# 09_iMX_8X_SD_CARD_V2X.net
KiCad netlist of a schematic drawn in Altium Designer
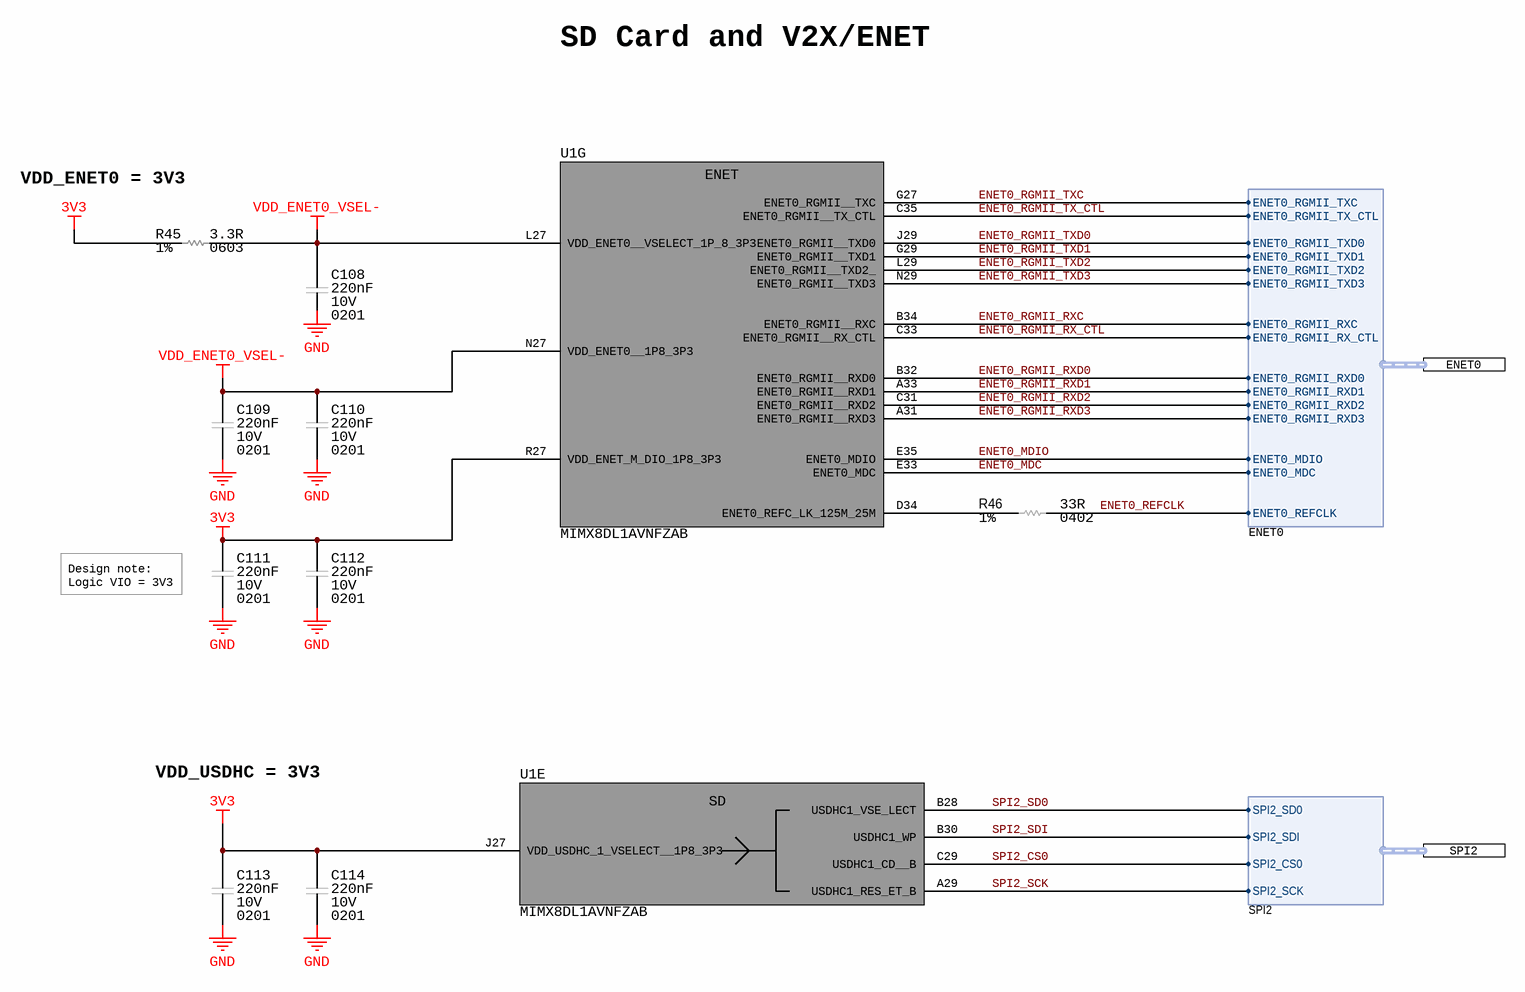
[diagram p0: 09_iMX 8X_SD CARD & V2X.SchDoc]

(export (version "E")
  (design (tool "Eeschema 10.0.6"))
  (components
    (comp (ref "C108")
      (value "LMK063BJ224MP-F")
      (footprint "CAP_0201_CAPC0603X03N")
      (description "Multilayer Ceramic Capacitors (High dielectric type), 10V, 0.22 uF, ± 20 %, 0201, X5R, RoHS")
      (fields
        (field (name "MANUFACTURER") "Taiyo Yuden")
        (field (name "TOLERANCE") "20%")
        (field (name "VOLTAGE RATING (DC)") "10V")
        (field (name "CAPACITANCE") "220nF")
        (field (name "CASE/PACKAGE") "0201")
      )
      (libsource (lib "Electronic Devices_LIB") (part "CAP_0.22UF_10V_X5R_0201"))
    )
    (comp (ref "C109")
      (value "LMK063BJ224MP-F")
      (footprint "CAP_0201_CAPC0603X03N")
      (description "Multilayer Ceramic Capacitors (High dielectric type), 10V, 0.22 uF, ± 20 %, 0201, X5R, RoHS")
      (fields
        (field (name "MANUFACTURER") "Taiyo Yuden")
        (field (name "TOLERANCE") "20%")
        (field (name "VOLTAGE RATING (DC)") "10V")
        (field (name "CAPACITANCE") "220nF")
        (field (name "CASE/PACKAGE") "0201")
      )
      (libsource (lib "Electronic Devices_LIB") (part "CAP_0.22UF_10V_X5R_0201"))
    )
    (comp (ref "C110")
      (value "LMK063BJ224MP-F")
      (footprint "CAP_0201_CAPC0603X03N")
      (description "Multilayer Ceramic Capacitors (High dielectric type), 10V, 0.22 uF, ± 20 %, 0201, X5R, RoHS")
      (fields
        (field (name "MANUFACTURER") "Taiyo Yuden")
        (field (name "TOLERANCE") "20%")
        (field (name "VOLTAGE RATING (DC)") "10V")
        (field (name "CAPACITANCE") "220nF")
        (field (name "CASE/PACKAGE") "0201")
      )
      (libsource (lib "Electronic Devices_LIB") (part "CAP_0.22UF_10V_X5R_0201"))
    )
    (comp (ref "C111")
      (value "LMK063BJ224MP-F")
      (footprint "CAP_0201_CAPC0603X03N")
      (description "Multilayer Ceramic Capacitors (High dielectric type), 10V, 0.22 uF, ± 20 %, 0201, X5R, RoHS")
      (fields
        (field (name "MANUFACTURER") "Taiyo Yuden")
        (field (name "TOLERANCE") "20%")
        (field (name "VOLTAGE RATING (DC)") "10V")
        (field (name "CAPACITANCE") "220nF")
        (field (name "CASE/PACKAGE") "0201")
      )
      (libsource (lib "Electronic Devices_LIB") (part "CAP_0.22UF_10V_X5R_0201"))
    )
    (comp (ref "C112")
      (value "LMK063BJ224MP-F")
      (footprint "CAP_0201_CAPC0603X03N")
      (description "Multilayer Ceramic Capacitors (High dielectric type), 10V, 0.22 uF, ± 20 %, 0201, X5R, RoHS")
      (fields
        (field (name "MANUFACTURER") "Taiyo Yuden")
        (field (name "TOLERANCE") "20%")
        (field (name "VOLTAGE RATING (DC)") "10V")
        (field (name "CAPACITANCE") "220nF")
        (field (name "CASE/PACKAGE") "0201")
      )
      (libsource (lib "Electronic Devices_LIB") (part "CAP_0.22UF_10V_X5R_0201"))
    )
    (comp (ref "C113")
      (value "LMK063BJ224MP-F")
      (footprint "CAP_0201_CAPC0603X03N")
      (description "Multilayer Ceramic Capacitors (High dielectric type), 10V, 0.22 uF, ± 20 %, 0201, X5R, RoHS")
      (fields
        (field (name "MANUFACTURER") "Taiyo Yuden")
        (field (name "TOLERANCE") "20%")
        (field (name "VOLTAGE RATING (DC)") "10V")
        (field (name "CAPACITANCE") "220nF")
        (field (name "CASE/PACKAGE") "0201")
      )
      (libsource (lib "Electronic Devices_LIB") (part "CAP_0.22UF_10V_X5R_0201"))
    )
    (comp (ref "C114")
      (value "LMK063BJ224MP-F")
      (footprint "CAP_0201_CAPC0603X03N")
      (description "Multilayer Ceramic Capacitors (High dielectric type), 10V, 0.22 uF, ± 20 %, 0201, X5R, RoHS")
      (fields
        (field (name "MANUFACTURER") "Taiyo Yuden")
        (field (name "TOLERANCE") "20%")
        (field (name "VOLTAGE RATING (DC)") "10V")
        (field (name "CAPACITANCE") "220nF")
        (field (name "CASE/PACKAGE") "0201")
      )
      (libsource (lib "Electronic Devices_LIB") (part "CAP_0.22UF_10V_X5R_0201"))
    )
    (comp (ref "R45")
      (value "RK73H1JTTD3R30F")
      (footprint "RES_0603_RESC1608X04N")
      (description "Thick Film Chip Resistor 0603 SMD 3.3 Ohm 1% 0.125W(1/8W) 200ppm/C")
      (fields
        (field (name "MANUFACTURER") "KOA Speer")
        (field (name "TOLERANCE") "1%")
        (field (name "RESISTANCE") "3.3R")
        (field (name "CASE CODE (IMPERIAL)") "0603")
      )
      (libsource (lib "Electronic Devices_LIB") (part "RES_3.3R_1%_125mW_0603"))
    )
    (comp (ref "R46")
      (value "RC0402FR-0733RL")
      (footprint "RES_0402_RESC1005X04N")
      (description "SMD Chip Resistor, 33 Ohm, ± 1%, 62.5 mW, 0402 [1005 Metric], Thick Film, General Purpose")
      (fields
        (field (name "MANUFACTURER") "Yageo")
        (field (name "TOLERANCE") "1%")
        (field (name "RESISTANCE") "33R")
        (field (name "CASE/PACKAGE") "0402")
      )
      (libsource (lib "Electronic Devices_LIB") (part "RES_33R_1%_62.5mW_0402"))
    )
    (comp (ref "U1")
      (value "MIMX8DL1AVNFZAB")
      (footprint "MIMX8DL1AVNFZAB")
      (description "I.MX8 Dxl 15SQ / Tray Rohs Compliant: Yes")
      (fields (field (name "MANUFACTURER") "NXP Semiconductors"))
      (libsource (lib "Electronic Devices_LIB") (part "IC_MPU_ARM_1.2GHz_MIMX8DL1AVNFZAB"))
    )
  )
  (nets
    (net (code "3") (name "/ENET0_MDC") (class "Default")
      (node (ref "U1") (pin "E33") (pinfunction "ENET0_MDC_E33") (pintype "passive"))
    )
    (net (code "4") (name "/ENET0_MDIO") (class "Default")
      (node (ref "U1") (pin "E35") (pinfunction "ENET0_MDIO_E35") (pintype "passive"))
    )
    (net (code "5") (name "/ENET0_REFCLK") (class "Default")
      (node (ref "R46") (pin "2") (pinfunction "2_2") (pintype "passive"))
    )
    (net (code "6") (name "/ENET0_RGMII_RXC") (class "Default")
      (node (ref "U1") (pin "B34") (pinfunction "ENET0_RGMII__RXC_B34") (pintype "passive"))
    )
    (net (code "7") (name "/ENET0_RGMII_RXD0") (class "Default")
      (node (ref "U1") (pin "B32") (pinfunction "ENET0_RGMII__RXD0_B32") (pintype "passive"))
    )
    (net (code "8") (name "/ENET0_RGMII_RXD1") (class "Default")
      (node (ref "U1") (pin "A33") (pinfunction "ENET0_RGMII__RXD1_A33") (pintype "passive"))
    )
    (net (code "9") (name "/ENET0_RGMII_RXD2") (class "Default")
      (node (ref "U1") (pin "C31") (pinfunction "ENET0_RGMII__RXD2_C31") (pintype "passive"))
    )
    (net (code "10") (name "/ENET0_RGMII_RXD3") (class "Default")
      (node (ref "U1") (pin "A31") (pinfunction "ENET0_RGMII__RXD3_A31") (pintype "passive"))
    )
    (net (code "11") (name "/ENET0_RGMII_RX_CTL") (class "Default")
      (node (ref "U1") (pin "C33") (pinfunction "ENET0_RGMII__RX_CTL_C33") (pintype "passive"))
    )
    (net (code "12") (name "/ENET0_RGMII_TXC") (class "Default")
      (node (ref "U1") (pin "G27") (pinfunction "ENET0_RGMII__TXC_G27") (pintype "passive"))
    )
    (net (code "13") (name "/ENET0_RGMII_TXD0") (class "Default")
      (node (ref "U1") (pin "J29") (pinfunction "ENET0_RGMII__TXD0_J29") (pintype "passive"))
    )
    (net (code "14") (name "/ENET0_RGMII_TXD1") (class "Default")
      (node (ref "U1") (pin "G29") (pinfunction "ENET0_RGMII__TXD1_G29") (pintype "passive"))
    )
    (net (code "15") (name "/ENET0_RGMII_TXD2") (class "Default")
      (node (ref "U1") (pin "L29") (pinfunction "ENET0_RGMII__TXD2__L29") (pintype "passive"))
    )
    (net (code "16") (name "/ENET0_RGMII_TXD3") (class "Default")
      (node (ref "U1") (pin "N29") (pinfunction "ENET0_RGMII__TXD3_N29") (pintype "passive"))
    )
    (net (code "17") (name "/ENET0_RGMII_TX_CTL") (class "Default")
      (node (ref "U1") (pin "C35") (pinfunction "ENET0_RGMII__TX_CTL_C35") (pintype "passive"))
    )
    (net (code "18") (name "/SPI2_CS0") (class "Default")
      (node (ref "U1") (pin "C29") (pinfunction "USDHC1_CD__B_C29") (pintype "passive"))
    )
    (net (code "19") (name "/SPI2_SCK") (class "Default")
      (node (ref "U1") (pin "A29") (pinfunction "USDHC1_RES_ET_B_A29") (pintype "passive"))
    )
    (net (code "20") (name "/SPI2_SD0") (class "Default")
      (node (ref "U1") (pin "B28") (pinfunction "USDHC1_VSE_LECT_B28") (pintype "passive"))
    )
    (net (code "21") (name "/SPI2_SDI") (class "Default")
      (node (ref "U1") (pin "B30") (pinfunction "USDHC1_WP_B30") (pintype "passive"))
    )
    (net (code "24") (name "3V3") (class "Default")
      (node (ref "C111") (pin "2") (pinfunction "2_2") (pintype "passive"))
      (node (ref "C112") (pin "2") (pinfunction "2_2") (pintype "passive"))
      (node (ref "C113") (pin "2") (pinfunction "2_2") (pintype "passive"))
      (node (ref "C114") (pin "2") (pinfunction "2_2") (pintype "passive"))
      (node (ref "R45") (pin "1") (pinfunction "1_1") (pintype "passive"))
      (node (ref "U1") (pin "J27") (pinfunction "VDD_USDHC_1_VSELECT__1P8_3P3_J27") (pintype "passive"))
      (node (ref "U1") (pin "R27") (pinfunction "VDD_ENET_M_DIO_1P8_3P3_R27") (pintype "passive"))
    )
    (net (code "25") (name "GND") (class "Default")
      (node (ref "C108") (pin "1") (pinfunction "1_1") (pintype "passive"))
      (node (ref "C109") (pin "1") (pinfunction "1_1") (pintype "passive"))
      (node (ref "C110") (pin "1") (pinfunction "1_1") (pintype "passive"))
      (node (ref "C111") (pin "1") (pinfunction "1_1") (pintype "passive"))
      (node (ref "C112") (pin "1") (pinfunction "1_1") (pintype "passive"))
      (node (ref "C113") (pin "1") (pinfunction "1_1") (pintype "passive"))
      (node (ref "C114") (pin "1") (pinfunction "1_1") (pintype "passive"))
    )
    (net (code "26") (name "Net-(U1G-ENET0_REFC_LK_125M_25M)") (class "Default")
      (node (ref "R46") (pin "1") (pinfunction "1_1") (pintype "passive"))
      (node (ref "U1") (pin "D34") (pinfunction "ENET0_REFC_LK_125M_25M_D34") (pintype "passive"))
    )
    (net (code "27") (name "VDD_ENET0_VSEL-") (class "Default")
      (node (ref "C108") (pin "2") (pinfunction "2_2") (pintype "passive"))
      (node (ref "C109") (pin "2") (pinfunction "2_2") (pintype "passive"))
      (node (ref "C110") (pin "2") (pinfunction "2_2") (pintype "passive"))
      (node (ref "R45") (pin "2") (pinfunction "2_2") (pintype "passive"))
      (node (ref "U1") (pin "L27") (pinfunction "VDD_ENET0__VSELECT_1P_8_3P3_L27") (pintype "passive"))
      (node (ref "U1") (pin "N27") (pinfunction "VDD_ENET0__1P8_3P3_N27") (pintype "passive"))
    )
  )
)
